# CAN_Wake_Up.net
KiCad netlist of a schematic drawn in EAGLE
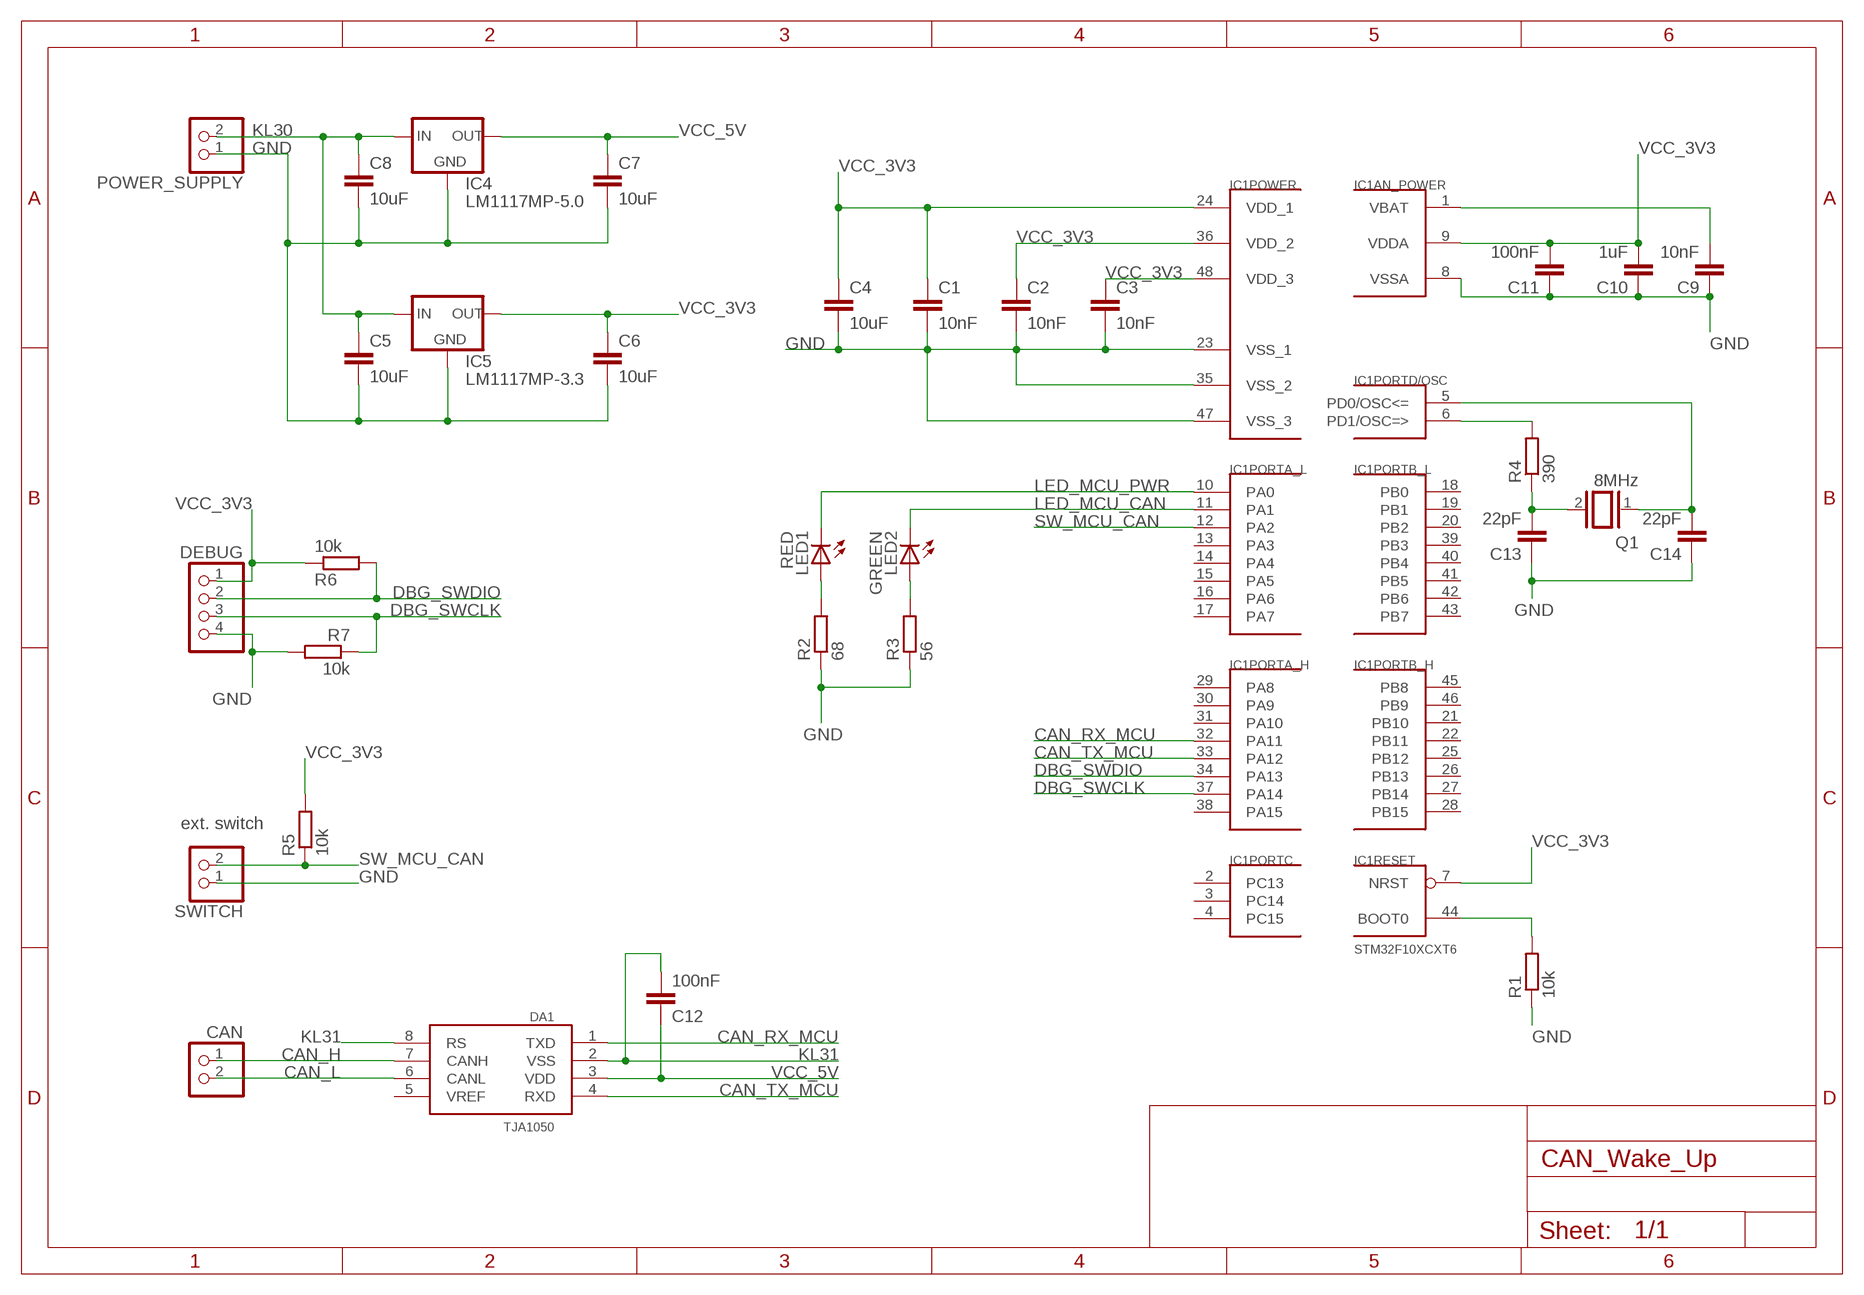
[diagram p0: schematic, sheet 1]

(export (version "E")
  (design (tool "Eeschema 10.0.6"))
  (components
    (comp (ref "C1")
      (value "10nF")
      (footprint "eagle-import:C0805")
      (libsource (lib "eagle-import") (part "C-EUC0805"))
    )
    (comp (ref "C2")
      (value "10nF")
      (footprint "eagle-import:C0805")
      (libsource (lib "eagle-import") (part "C-EUC0805"))
    )
    (comp (ref "C3")
      (value "10nF")
      (footprint "eagle-import:C0805")
      (libsource (lib "eagle-import") (part "C-EUC0805"))
    )
    (comp (ref "C4")
      (value "10uF")
      (footprint "eagle-import:C0805")
      (libsource (lib "eagle-import") (part "C-EUC0805"))
    )
    (comp (ref "C5")
      (value "10uF")
      (footprint "eagle-import:C0805")
      (libsource (lib "eagle-import") (part "C-EUC0805"))
    )
    (comp (ref "C6")
      (value "10uF")
      (footprint "eagle-import:C0805")
      (libsource (lib "eagle-import") (part "C-EUC0805"))
    )
    (comp (ref "C7")
      (value "10uF")
      (footprint "eagle-import:C0805")
      (libsource (lib "eagle-import") (part "C-EUC0805"))
    )
    (comp (ref "C8")
      (value "10uF")
      (footprint "eagle-import:C0805")
      (libsource (lib "eagle-import") (part "C-EUC0805"))
    )
    (comp (ref "C9")
      (value "10nF")
      (footprint "eagle-import:C0805")
      (libsource (lib "eagle-import") (part "C-EUC0805"))
    )
    (comp (ref "C10")
      (value "1uF")
      (footprint "eagle-import:C0805")
      (libsource (lib "eagle-import") (part "C-EUC0805"))
    )
    (comp (ref "C11")
      (value "100nF")
      (footprint "eagle-import:C0805")
      (libsource (lib "eagle-import") (part "C-EUC0805"))
    )
    (comp (ref "C12")
      (value "100nF")
      (footprint "eagle-import:C0805")
      (libsource (lib "eagle-import") (part "C-EUC0805"))
    )
    (comp (ref "C13")
      (value "22pF")
      (footprint "eagle-import:C0805")
      (libsource (lib "eagle-import") (part "C-EUC0805"))
    )
    (comp (ref "C14")
      (value "22pF")
      (footprint "eagle-import:C0805")
      (libsource (lib "eagle-import") (part "C-EUC0805"))
    )
    (comp (ref "CAN")
      (value "PINHD-1X2")
      (footprint "eagle-import:1X02")
      (libsource (lib "eagle-import") (part "PINHD-1X2"))
    )
    (comp (ref "DA1")
      (value "TJA1050")
      (footprint "eagle-import:SO08")
      (libsource (lib "eagle-import") (part "TJA1050"))
    )
    (comp (ref "DEBUG")
      (value "PINHD-1X4")
      (footprint "eagle-import:1X04")
      (libsource (lib "eagle-import") (part "PINHD-1X4"))
    )
    (comp (ref "IC1")
      (value "STM32F10XCXT6")
      (footprint "eagle-import:TQFP48")
      (libsource (lib "eagle-import") (part "STM32F10XCXT6"))
    )
    (comp (ref "IC4")
      (value "LM1117MP-5.0")
      (footprint "eagle-import:SOT223")
      (fields (field (name "MF") "Texas Instruments"))
      (libsource (lib "eagle-import") (part "LM1117?-MP5.0"))
    )
    (comp (ref "IC5")
      (value "LM1117MP-3.3")
      (footprint "eagle-import:SOT223")
      (fields (field (name "MF") "Texas Instruments"))
      (libsource (lib "eagle-import") (part "LM1117?-MP3.3"))
    )
    (comp (ref "LED1")
      (value "RED")
      (footprint "eagle-import:LED3MM")
      (libsource (lib "eagle-import") (part "LED3MM"))
    )
    (comp (ref "LED2")
      (value "GREEN")
      (footprint "eagle-import:LED3MM")
      (libsource (lib "eagle-import") (part "LED3MM"))
    )
    (comp (ref "POWER_SUPPLY")
      (value "PINHD-1X2")
      (footprint "eagle-import:1X02")
      (libsource (lib "eagle-import") (part "PINHD-1X2"))
    )
    (comp (ref "Q1")
      (value "8MHz")
      (footprint "eagle-import:Q")
      (libsource (lib "eagle-import") (part "XTAL"))
    )
    (comp (ref "R1")
      (value "10k")
      (footprint "eagle-import:R0805")
      (libsource (lib "eagle-import") (part "R-EU_R0805"))
    )
    (comp (ref "R2")
      (value "68")
      (footprint "eagle-import:R0805")
      (libsource (lib "eagle-import") (part "R-EU_R0805"))
    )
    (comp (ref "R3")
      (value "56")
      (footprint "eagle-import:R0805")
      (libsource (lib "eagle-import") (part "R-EU_R0805"))
    )
    (comp (ref "R4")
      (value "390")
      (footprint "eagle-import:R0805")
      (libsource (lib "eagle-import") (part "R-EU_R0805"))
    )
    (comp (ref "R5")
      (value "10k")
      (footprint "eagle-import:R0805")
      (libsource (lib "eagle-import") (part "R-EU_R0805"))
    )
    (comp (ref "R6")
      (value "10k")
      (footprint "eagle-import:R0805")
      (libsource (lib "eagle-import") (part "R-EU_R0805"))
    )
    (comp (ref "R7")
      (value "10k")
      (footprint "eagle-import:R0805")
      (libsource (lib "eagle-import") (part "R-EU_R0805"))
    )
    (comp (ref "SWITCH")
      (value "PINHD-1X2")
      (footprint "eagle-import:1X02")
      (libsource (lib "eagle-import") (part "PINHD-1X2"))
    )
  )
  (nets
    (net (code "1") (name "/CAN_H") (class "Default")
      (node (ref "CAN") (pin "1") (pinfunction "1_1") (pintype "passive"))
      (node (ref "DA1") (pin "7") (pinfunction "CANH_7") (pintype "bidirectional"))
    )
    (net (code "2") (name "/CAN_L") (class "Default")
      (node (ref "CAN") (pin "2") (pinfunction "2_2") (pintype "passive"))
      (node (ref "DA1") (pin "6") (pinfunction "CANL_6") (pintype "bidirectional"))
    )
    (net (code "3") (name "/CAN_RX_MCU") (class "Default")
      (node (ref "DA1") (pin "1") (pinfunction "TXD_1") (pintype "input"))
      (node (ref "IC1") (pin "32") (pinfunction "PA11_32") (pintype "bidirectional"))
    )
    (net (code "4") (name "/CAN_TX_MCU") (class "Default")
      (node (ref "DA1") (pin "4") (pinfunction "RXD_4") (pintype "output"))
      (node (ref "IC1") (pin "33") (pinfunction "PA12_33") (pintype "bidirectional"))
    )
    (net (code "5") (name "/DBG_SWCLK") (class "Default")
      (node (ref "DEBUG") (pin "3") (pinfunction "3_3") (pintype "passive"))
      (node (ref "IC1") (pin "37") (pinfunction "PA14_37") (pintype "bidirectional"))
      (node (ref "R7") (pin "1") (pinfunction "1_1") (pintype "passive"))
    )
    (net (code "6") (name "/DBG_SWDIO") (class "Default")
      (node (ref "DEBUG") (pin "2") (pinfunction "2_2") (pintype "passive"))
      (node (ref "IC1") (pin "34") (pinfunction "PA13_34") (pintype "bidirectional"))
      (node (ref "R6") (pin "2") (pinfunction "2_2") (pintype "passive"))
    )
    (net (code "7") (name "/GND") (class "Default")
      (node (ref "C1") (pin "2") (pinfunction "2_2") (pintype "passive"))
      (node (ref "C10") (pin "1") (pinfunction "1_1") (pintype "passive"))
      (node (ref "C11") (pin "1") (pinfunction "1_1") (pintype "passive"))
      (node (ref "C13") (pin "1") (pinfunction "1_1") (pintype "passive"))
      (node (ref "C14") (pin "1") (pinfunction "1_1") (pintype "passive"))
      (node (ref "C2") (pin "2") (pinfunction "2_2") (pintype "passive"))
      (node (ref "C3") (pin "2") (pinfunction "2_2") (pintype "passive"))
      (node (ref "C4") (pin "2") (pinfunction "2_2") (pintype "passive"))
      (node (ref "C5") (pin "2") (pinfunction "2_2") (pintype "passive"))
      (node (ref "C6") (pin "2") (pinfunction "2_2") (pintype "passive"))
      (node (ref "C7") (pin "2") (pinfunction "2_2") (pintype "passive"))
      (node (ref "C8") (pin "2") (pinfunction "2_2") (pintype "passive"))
      (node (ref "C9") (pin "1") (pinfunction "1_1") (pintype "passive"))
      (node (ref "DEBUG") (pin "4") (pinfunction "4_4") (pintype "passive"))
      (node (ref "IC1") (pin "23") (pinfunction "VSS_1_23") (pintype "power_in"))
      (node (ref "IC1") (pin "35") (pinfunction "VSS_2_35") (pintype "power_in"))
      (node (ref "IC1") (pin "47") (pinfunction "VSS_3_47") (pintype "power_in"))
      (node (ref "IC1") (pin "8") (pinfunction "VSSA_8") (pintype "power_in"))
      (node (ref "IC4") (pin "1") (pinfunction "GND_1") (pintype "input"))
      (node (ref "IC5") (pin "1") (pinfunction "GND_1") (pintype "input"))
      (node (ref "POWER_SUPPLY") (pin "1") (pinfunction "1_1") (pintype "passive"))
      (node (ref "R1") (pin "1") (pinfunction "1_1") (pintype "passive"))
      (node (ref "R2") (pin "1") (pinfunction "1_1") (pintype "passive"))
      (node (ref "R3") (pin "1") (pinfunction "1_1") (pintype "passive"))
      (node (ref "R7") (pin "2") (pinfunction "2_2") (pintype "passive"))
      (node (ref "SWITCH") (pin "1") (pinfunction "1_1") (pintype "passive"))
    )
    (net (code "8") (name "/KL30") (class "Default")
      (node (ref "C5") (pin "1") (pinfunction "1_1") (pintype "passive"))
      (node (ref "C8") (pin "1") (pinfunction "1_1") (pintype "passive"))
      (node (ref "IC4") (pin "3") (pinfunction "IN_3") (pintype "input"))
      (node (ref "IC5") (pin "3") (pinfunction "IN_3") (pintype "input"))
      (node (ref "POWER_SUPPLY") (pin "2") (pinfunction "2_2") (pintype "passive"))
    )
    (net (code "9") (name "/KL31") (class "Default")
      (node (ref "C12") (pin "2") (pinfunction "2_2") (pintype "passive"))
      (node (ref "DA1") (pin "2") (pinfunction "VSS_2") (pintype "power_in"))
      (node (ref "DA1") (pin "8") (pinfunction "RS_8") (pintype "input"))
    )
    (net (code "10") (name "/LED_MCU_CAN") (class "Default")
      (node (ref "IC1") (pin "11") (pinfunction "PA1_11") (pintype "bidirectional"))
      (node (ref "LED2") (pin "K") (pinfunction "C_K") (pintype "passive"))
    )
    (net (code "11") (name "/LED_MCU_PWR") (class "Default")
      (node (ref "IC1") (pin "10") (pinfunction "PA0_10") (pintype "bidirectional"))
      (node (ref "LED1") (pin "K") (pinfunction "C_K") (pintype "passive"))
    )
    (net (code "12") (name "/SW_MCU_CAN") (class "Default")
      (node (ref "IC1") (pin "12") (pinfunction "PA2_12") (pintype "bidirectional"))
      (node (ref "R5") (pin "1") (pinfunction "1_1") (pintype "passive"))
      (node (ref "SWITCH") (pin "2") (pinfunction "2_2") (pintype "passive"))
    )
    (net (code "13") (name "/VCC_3V3") (class "Default")
      (node (ref "C1") (pin "1") (pinfunction "1_1") (pintype "passive"))
      (node (ref "C10") (pin "2") (pinfunction "2_2") (pintype "passive"))
      (node (ref "C11") (pin "2") (pinfunction "2_2") (pintype "passive"))
      (node (ref "C2") (pin "1") (pinfunction "1_1") (pintype "passive"))
      (node (ref "C3") (pin "1") (pinfunction "1_1") (pintype "passive"))
      (node (ref "C4") (pin "1") (pinfunction "1_1") (pintype "passive"))
      (node (ref "C6") (pin "1") (pinfunction "1_1") (pintype "passive"))
      (node (ref "DEBUG") (pin "1") (pinfunction "1_1") (pintype "passive"))
      (node (ref "IC1") (pin "24") (pinfunction "VDD_1_24") (pintype "power_in"))
      (node (ref "IC1") (pin "36") (pinfunction "VDD_2_36") (pintype "power_in"))
      (node (ref "IC1") (pin "48") (pinfunction "VDD_3_48") (pintype "power_in"))
      (node (ref "IC1") (pin "7") (pinfunction "NRST_7") (pintype "input"))
      (node (ref "IC1") (pin "9") (pinfunction "VDDA_9") (pintype "power_in"))
      (node (ref "IC5") (pin "2") (pinfunction "OUT_2") (pintype "passive"))
      (node (ref "IC5") (pin "4") (pinfunction "OUT_4") (pintype "passive"))
      (node (ref "R5") (pin "2") (pinfunction "2_2") (pintype "passive"))
      (node (ref "R6") (pin "1") (pinfunction "1_1") (pintype "passive"))
    )
    (net (code "14") (name "/VCC_5V") (class "Default")
      (node (ref "C12") (pin "1") (pinfunction "1_1") (pintype "passive"))
      (node (ref "C7") (pin "1") (pinfunction "1_1") (pintype "passive"))
      (node (ref "DA1") (pin "3") (pinfunction "VDD_3") (pintype "power_in"))
      (node (ref "IC4") (pin "2") (pinfunction "OUT_2") (pintype "passive"))
      (node (ref "IC4") (pin "4") (pinfunction "OUT_4") (pintype "passive"))
    )
    (net (code "15") (name "Net-(C13-Pad2)") (class "Default")
      (node (ref "C13") (pin "2") (pinfunction "2_2") (pintype "passive"))
      (node (ref "Q1") (pin "2") (pinfunction "2_2") (pintype "passive"))
      (node (ref "R4") (pin "1") (pinfunction "1_1") (pintype "passive"))
    )
    (net (code "16") (name "Net-(IC1A-VBAT)") (class "Default")
      (node (ref "C9") (pin "2") (pinfunction "2_2") (pintype "passive"))
      (node (ref "IC1") (pin "1") (pinfunction "VBAT_1") (pintype "power_in"))
    )
    (net (code "17") (name "Net-(IC1G-PD0{slash}OSC<=)") (class "Default")
      (node (ref "C14") (pin "2") (pinfunction "2_2") (pintype "passive"))
      (node (ref "IC1") (pin "5") (pinfunction "PD0/OSC<=_5") (pintype "bidirectional"))
      (node (ref "Q1") (pin "1") (pinfunction "1_1") (pintype "passive"))
    )
    (net (code "18") (name "Net-(IC1G-PD1{slash}OSC=>)") (class "Default")
      (node (ref "IC1") (pin "6") (pinfunction "PD1/OSC=>_6") (pintype "bidirectional"))
      (node (ref "R4") (pin "2") (pinfunction "2_2") (pintype "passive"))
    )
    (net (code "19") (name "Net-(IC1I-BOOT0)") (class "Default")
      (node (ref "IC1") (pin "44") (pinfunction "BOOT0_44") (pintype "input"))
      (node (ref "R1") (pin "2") (pinfunction "2_2") (pintype "passive"))
    )
    (net (code "20") (name "Net-(LED1-PadA)") (class "Default")
      (node (ref "LED1") (pin "A") (pinfunction "A_A") (pintype "passive"))
      (node (ref "R2") (pin "2") (pinfunction "2_2") (pintype "passive"))
    )
    (net (code "21") (name "Net-(LED2-PadA)") (class "Default")
      (node (ref "LED2") (pin "A") (pinfunction "A_A") (pintype "passive"))
      (node (ref "R3") (pin "2") (pinfunction "2_2") (pintype "passive"))
    )
    (net (code "22") (name "unconnected-(DA1-VREF-Pad5)") (class "Default")
      (node (ref "DA1") (pin "5") (pinfunction "VREF_5") (pintype "passive"))
    )
    (net (code "23") (name "unconnected-(IC1B-PA8-Pad29)") (class "Default")
      (node (ref "IC1") (pin "29") (pinfunction "PA8_29") (pintype "bidirectional"))
    )
    (net (code "24") (name "unconnected-(IC1B-PA9-Pad30)") (class "Default")
      (node (ref "IC1") (pin "30") (pinfunction "PA9_30") (pintype "bidirectional"))
    )
    (net (code "25") (name "unconnected-(IC1B-PA10-Pad31)") (class "Default")
      (node (ref "IC1") (pin "31") (pinfunction "PA10_31") (pintype "bidirectional"))
    )
    (net (code "26") (name "unconnected-(IC1B-PA15-Pad38)") (class "Default")
      (node (ref "IC1") (pin "38") (pinfunction "PA15_38") (pintype "bidirectional"))
    )
    (net (code "27") (name "unconnected-(IC1C-PA3-Pad13)") (class "Default")
      (node (ref "IC1") (pin "13") (pinfunction "PA3_13") (pintype "bidirectional"))
    )
    (net (code "28") (name "unconnected-(IC1C-PA4-Pad14)") (class "Default")
      (node (ref "IC1") (pin "14") (pinfunction "PA4_14") (pintype "bidirectional"))
    )
    (net (code "29") (name "unconnected-(IC1C-PA5-Pad15)") (class "Default")
      (node (ref "IC1") (pin "15") (pinfunction "PA5_15") (pintype "bidirectional"))
    )
    (net (code "30") (name "unconnected-(IC1C-PA6-Pad16)") (class "Default")
      (node (ref "IC1") (pin "16") (pinfunction "PA6_16") (pintype "bidirectional"))
    )
    (net (code "31") (name "unconnected-(IC1C-PA7-Pad17)") (class "Default")
      (node (ref "IC1") (pin "17") (pinfunction "PA7_17") (pintype "bidirectional"))
    )
    (net (code "32") (name "unconnected-(IC1D-PB8-Pad45)") (class "Default")
      (node (ref "IC1") (pin "45") (pinfunction "PB8_45") (pintype "bidirectional"))
    )
    (net (code "33") (name "unconnected-(IC1D-PB9-Pad46)") (class "Default")
      (node (ref "IC1") (pin "46") (pinfunction "PB9_46") (pintype "bidirectional"))
    )
    (net (code "34") (name "unconnected-(IC1D-PB10-Pad21)") (class "Default")
      (node (ref "IC1") (pin "21") (pinfunction "PB10_21") (pintype "bidirectional"))
    )
    (net (code "35") (name "unconnected-(IC1D-PB11-Pad22)") (class "Default")
      (node (ref "IC1") (pin "22") (pinfunction "PB11_22") (pintype "bidirectional"))
    )
    (net (code "36") (name "unconnected-(IC1D-PB12-Pad25)") (class "Default")
      (node (ref "IC1") (pin "25") (pinfunction "PB12_25") (pintype "bidirectional"))
    )
    (net (code "37") (name "unconnected-(IC1D-PB13-Pad26)") (class "Default")
      (node (ref "IC1") (pin "26") (pinfunction "PB13_26") (pintype "bidirectional"))
    )
    (net (code "38") (name "unconnected-(IC1D-PB14-Pad27)") (class "Default")
      (node (ref "IC1") (pin "27") (pinfunction "PB14_27") (pintype "bidirectional"))
    )
    (net (code "39") (name "unconnected-(IC1D-PB15-Pad28)") (class "Default")
      (node (ref "IC1") (pin "28") (pinfunction "PB15_28") (pintype "bidirectional"))
    )
    (net (code "40") (name "unconnected-(IC1E-PB0-Pad18)") (class "Default")
      (node (ref "IC1") (pin "18") (pinfunction "PB0_18") (pintype "bidirectional"))
    )
    (net (code "41") (name "unconnected-(IC1E-PB1-Pad19)") (class "Default")
      (node (ref "IC1") (pin "19") (pinfunction "PB1_19") (pintype "bidirectional"))
    )
    (net (code "42") (name "unconnected-(IC1E-PB2-Pad20)") (class "Default")
      (node (ref "IC1") (pin "20") (pinfunction "PB2_20") (pintype "bidirectional"))
    )
    (net (code "43") (name "unconnected-(IC1E-PB3-Pad39)") (class "Default")
      (node (ref "IC1") (pin "39") (pinfunction "PB3_39") (pintype "bidirectional"))
    )
    (net (code "44") (name "unconnected-(IC1E-PB4-Pad40)") (class "Default")
      (node (ref "IC1") (pin "40") (pinfunction "PB4_40") (pintype "bidirectional"))
    )
    (net (code "45") (name "unconnected-(IC1E-PB5-Pad41)") (class "Default")
      (node (ref "IC1") (pin "41") (pinfunction "PB5_41") (pintype "bidirectional"))
    )
    (net (code "46") (name "unconnected-(IC1E-PB6-Pad42)") (class "Default")
      (node (ref "IC1") (pin "42") (pinfunction "PB6_42") (pintype "bidirectional"))
    )
    (net (code "47") (name "unconnected-(IC1E-PB7-Pad43)") (class "Default")
      (node (ref "IC1") (pin "43") (pinfunction "PB7_43") (pintype "bidirectional"))
    )
    (net (code "48") (name "unconnected-(IC1F-PC13-Pad2)") (class "Default")
      (node (ref "IC1") (pin "2") (pinfunction "PC13_2") (pintype "bidirectional"))
    )
    (net (code "49") (name "unconnected-(IC1F-PC14-Pad3)") (class "Default")
      (node (ref "IC1") (pin "3") (pinfunction "PC14_3") (pintype "bidirectional"))
    )
    (net (code "50") (name "unconnected-(IC1F-PC15-Pad4)") (class "Default")
      (node (ref "IC1") (pin "4") (pinfunction "PC15_4") (pintype "bidirectional"))
    )
  )
)
